# Pure_ADSR.net
KiCad netlist of a schematic drawn in EAGLE
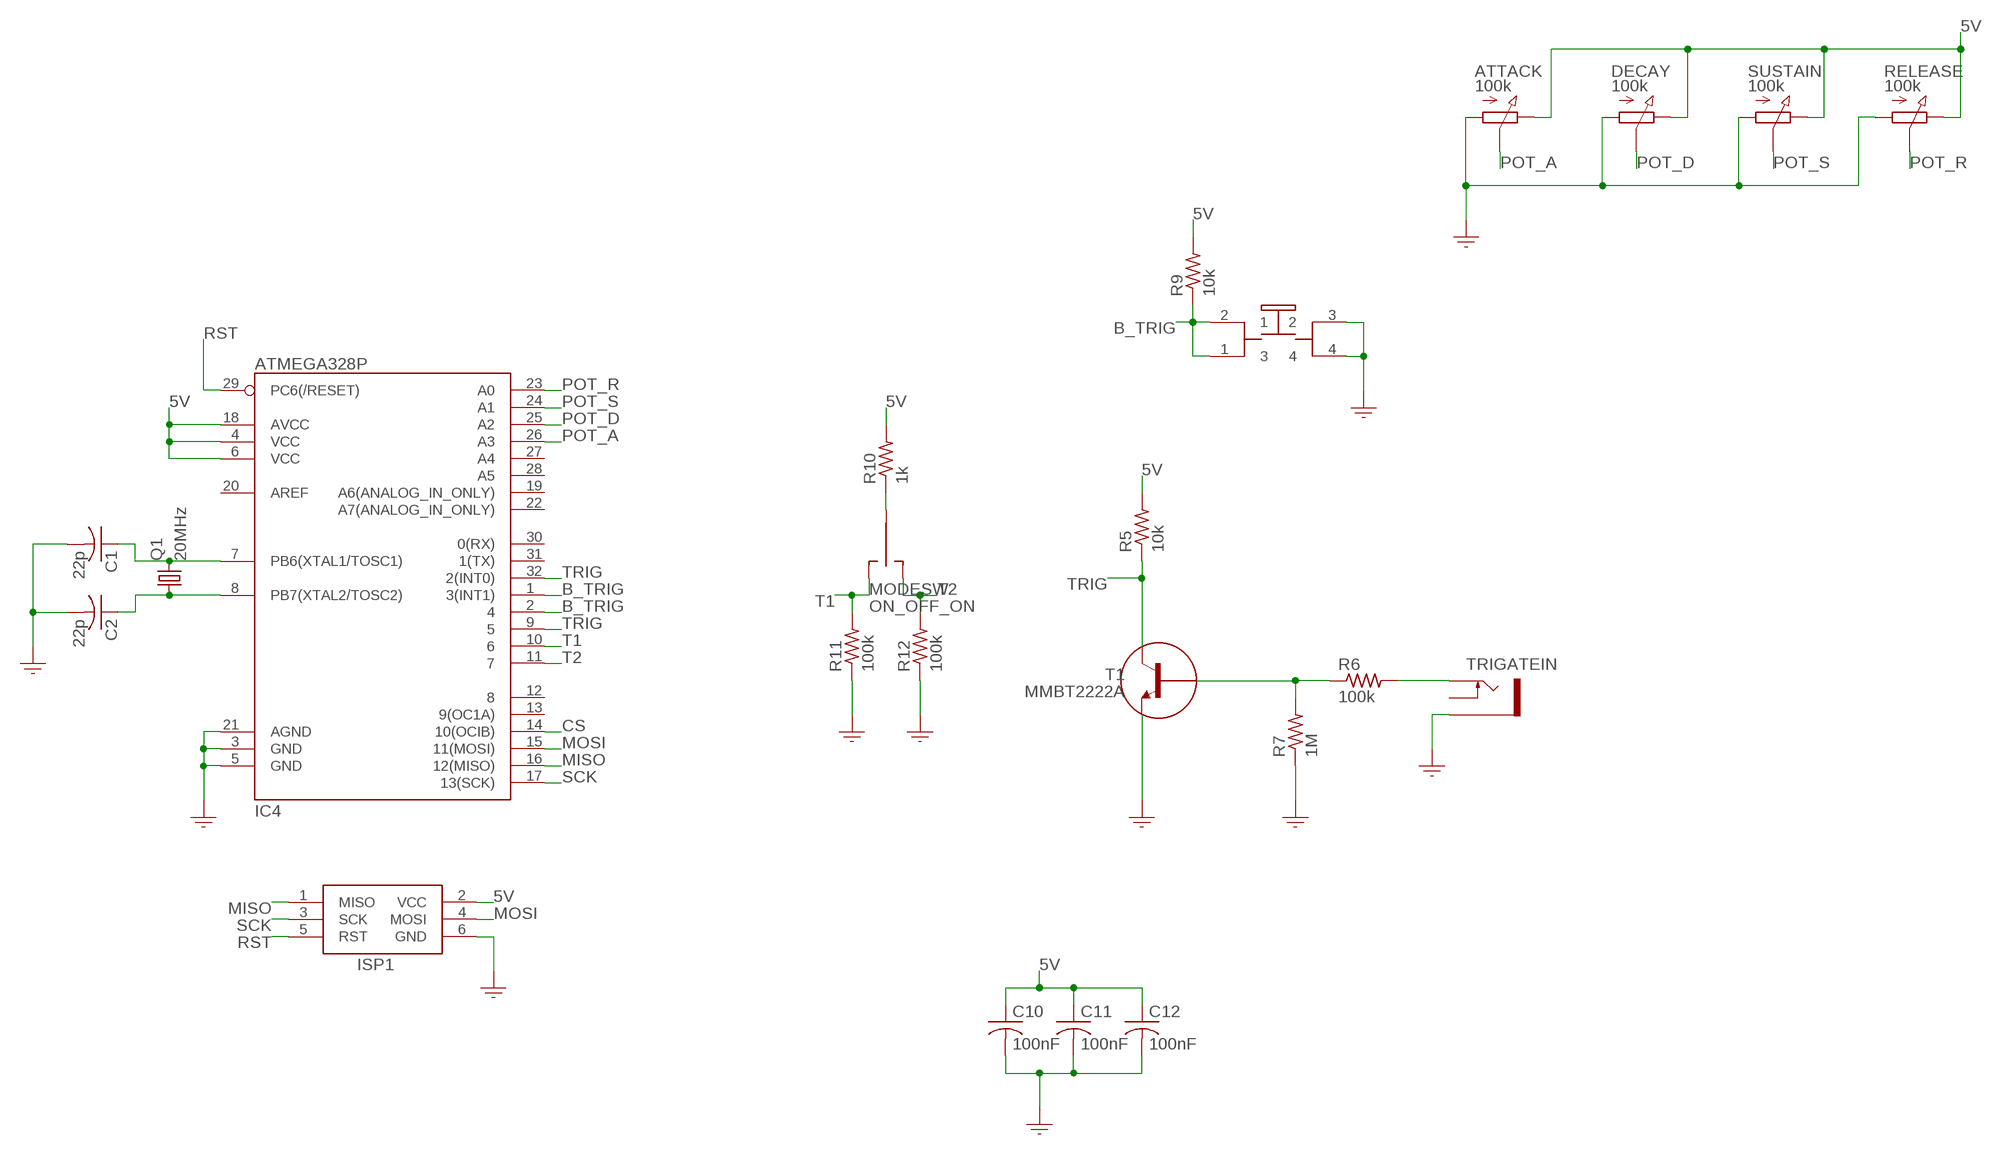
[diagram p0: schematic, sheet 1]
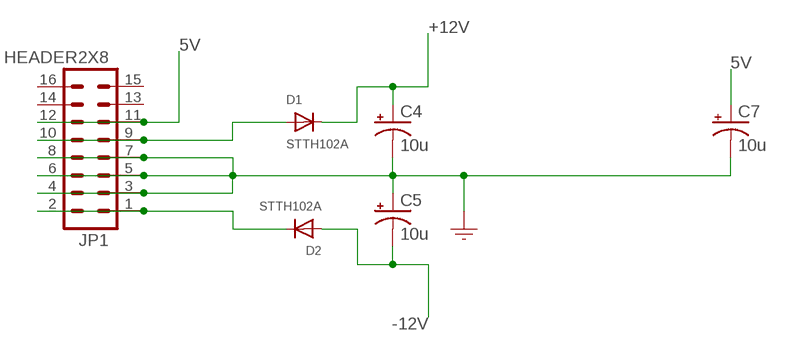
[diagram p1: schematic, sheet 2]
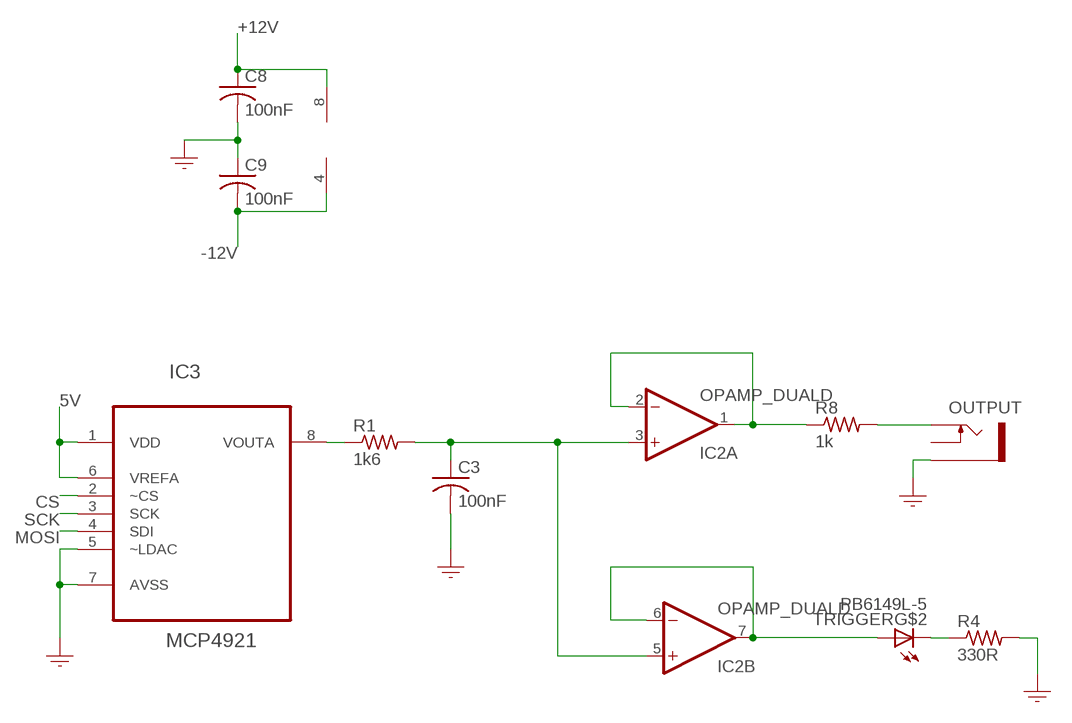
[diagram p2: schematic, sheet 3]

(export (version "E")
  (design (tool "Eeschema 10.0.6"))
  (components
    (comp (ref "C4")
      (value "10u")
      (footprint "eagle-import:153CLV-0505")
      (libsource (lib "eagle-import") (part "CAPACITOR_POL-US153CLV-0505"))
    )
    (comp (ref "C5")
      (value "10u")
      (footprint "eagle-import:153CLV-0505")
      (libsource (lib "eagle-import") (part "CAPACITOR_POL-US153CLV-0505"))
    )
    (comp (ref "C7")
      (value "10u")
      (footprint "eagle-import:153CLV-0505")
      (libsource (lib "eagle-import") (part "CAPACITOR_POL-US153CLV-0505"))
    )
    (comp (ref "D1")
      (value "STTH102A")
      (footprint "eagle-import:SMADIODE")
      (libsource (lib "eagle-import") (part "DIODESMA"))
    )
    (comp (ref "D2")
      (value "STTH102A")
      (footprint "eagle-import:SMADIODE")
      (libsource (lib "eagle-import") (part "DIODESMA"))
    )
    (comp (ref "JP1")
      (value "HEADER2X8")
      (footprint "eagle-import:POWER_SHROUDED")
      (libsource (lib "eagle-import") (part "HEADER2X8"))
    )
    (comp (ref "C3")
      (value "100nF")
      (footprint "eagle-import:C0805")
      (libsource (lib "eagle-import") (part "CAPACITOR-USC0805"))
    )
    (comp (ref "C8")
      (value "100nF")
      (footprint "eagle-import:C0805")
      (libsource (lib "eagle-import") (part "CAPACITOR-USC0805"))
    )
    (comp (ref "C9")
      (value "100nF")
      (footprint "eagle-import:C0805")
      (libsource (lib "eagle-import") (part "CAPACITOR-USC0805"))
    )
    (comp (ref "IC2")
      (value "OPAMP_DUALD")
      (footprint "eagle-import:SO08")
      (libsource (lib "eagle-import") (part "OPAMP_DUALD"))
    )
    (comp (ref "IC3")
      (value "MCP4921")
      (footprint "eagle-import:SOIC8")
      (libsource (lib "eagle-import") (part "DAC_SINGLE_12B_MCP4921"))
    )
    (comp (ref "OUTPUT")
      (value "SOCKET_MONO_3.5MMPJ301M-12")
      (footprint "eagle-import:PJ301M-12")
      (libsource (lib "eagle-import") (part "SOCKET_MONO_3.5MMPJ301M-12"))
    )
    (comp (ref "R1")
      (value "1k6")
      (footprint "eagle-import:R0805")
      (libsource (lib "eagle-import") (part "RESISTOR_USR0805"))
    )
    (comp (ref "R4")
      (value "330R")
      (footprint "eagle-import:R0805")
      (libsource (lib "eagle-import") (part "RESISTOR_USR0805"))
    )
    (comp (ref "R8")
      (value "1k")
      (footprint "eagle-import:R0805")
      (libsource (lib "eagle-import") (part "RESISTOR_USR0805"))
    )
    (comp (ref "TRIGGER")
      (value "PB6149L-5")
      (footprint "eagle-import:PB6149L")
      (libsource (lib "eagle-import") (part "SWITCH_PUSHBUTTON_LED"))
    )
    (comp (ref "ATTACK")
      (value "100k")
      (footprint "eagle-import:POTENTIOMETER_9MM")
      (libsource (lib "eagle-import") (part "RESISTOR_VARIABLE9MM_POT"))
    )
    (comp (ref "C1")
      (value "22p")
      (footprint "eagle-import:C0805")
      (libsource (lib "eagle-import") (part "CAPACITOR-USC0805"))
    )
    (comp (ref "C2")
      (value "22p")
      (footprint "eagle-import:C0805")
      (libsource (lib "eagle-import") (part "CAPACITOR-USC0805"))
    )
    (comp (ref "C10")
      (value "100nF")
      (footprint "eagle-import:C0805")
      (libsource (lib "eagle-import") (part "CAPACITOR-USC0805"))
    )
    (comp (ref "C11")
      (value "100nF")
      (footprint "eagle-import:C0805")
      (libsource (lib "eagle-import") (part "CAPACITOR-USC0805"))
    )
    (comp (ref "C12")
      (value "100nF")
      (footprint "eagle-import:C0805")
      (libsource (lib "eagle-import") (part "CAPACITOR-USC0805"))
    )
    (comp (ref "DECAY")
      (value "100k")
      (footprint "eagle-import:POTENTIOMETER_9MM")
      (libsource (lib "eagle-import") (part "RESISTOR_VARIABLE9MM_POT"))
    )
    (comp (ref "IC4")
      (value "ATMEGA328P")
      (footprint "eagle-import:TQFP32-08")
      (libsource (lib "eagle-import") (part "MICROPROCESSOR_ATMEGA328_SMT"))
    )
    (comp (ref "ISP1")
      (value "HEADER2X3-6")
      (footprint "eagle-import:AVRISP")
      (libsource (lib "eagle-import") (part "HEADER2X3-6"))
    )
    (comp (ref "MODESW")
      (value "ON_OFF_ON")
      (footprint "eagle-import:TOGGLE_SW")
      (libsource (lib "eagle-import") (part "SWITCH_TOGGLE_SPDT"))
    )
    (comp (ref "Q1")
      (value "20MHz")
      (footprint "eagle-import:HC49UP")
      (libsource (lib "eagle-import") (part "CRYSTALHC49UP"))
    )
    (comp (ref "R5")
      (value "10k")
      (footprint "eagle-import:R0805")
      (libsource (lib "eagle-import") (part "RESISTOR_USR0805"))
    )
    (comp (ref "R6")
      (value "100k")
      (footprint "eagle-import:R0805")
      (libsource (lib "eagle-import") (part "RESISTOR_USR0805"))
    )
    (comp (ref "R7")
      (value "1M")
      (footprint "eagle-import:R0805")
      (libsource (lib "eagle-import") (part "RESISTOR_USR0805"))
    )
    (comp (ref "R9")
      (value "10k")
      (footprint "eagle-import:R0805")
      (libsource (lib "eagle-import") (part "RESISTOR_USR0805"))
    )
    (comp (ref "R10")
      (value "1k")
      (footprint "eagle-import:R0805")
      (libsource (lib "eagle-import") (part "RESISTOR_USR0805"))
    )
    (comp (ref "R11")
      (value "100k")
      (footprint "eagle-import:R0805")
      (libsource (lib "eagle-import") (part "RESISTOR_USR0805"))
    )
    (comp (ref "R12")
      (value "100k")
      (footprint "eagle-import:R0805")
      (libsource (lib "eagle-import") (part "RESISTOR_USR0805"))
    )
    (comp (ref "RELEASE")
      (value "100k")
      (footprint "eagle-import:POTENTIOMETER_9MM")
      (libsource (lib "eagle-import") (part "RESISTOR_VARIABLE9MM_POT"))
    )
    (comp (ref "SUSTAIN")
      (value "100k")
      (footprint "eagle-import:POTENTIOMETER_9MM")
      (libsource (lib "eagle-import") (part "RESISTOR_VARIABLE9MM_POT"))
    )
    (comp (ref "T1")
      (value "MMBT2222A")
      (footprint "eagle-import:SOT23")
      (libsource (lib "eagle-import") (part "TRANSISTOR_NPNMMBT2222A"))
    )
    (comp (ref "TRIGATEIN")
      (value "SOCKET_MONO_3.5MMPJ301M-12")
      (footprint "eagle-import:PJ301M-12")
      (libsource (lib "eagle-import") (part "SOCKET_MONO_3.5MMPJ301M-12"))
    )
  )
  (nets
    (net (code "1") (name "+12V") (class "Default")
      (node (ref "C4") (pin "+") (pinfunction "+_+") (pintype "passive"))
      (node (ref "C8") (pin "1") (pinfunction "1_1") (pintype "passive"))
      (node (ref "D1") (pin "C") (pinfunction "C_C") (pintype "passive"))
      (node (ref "IC2") (pin "8") (pinfunction "V+_8") (pintype "power_in"))
    )
    (net (code "2") (name "-12V") (class "Default")
      (node (ref "C5") (pin "-") (pinfunction "-_-") (pintype "passive"))
      (node (ref "C9") (pin "2") (pinfunction "2_2") (pintype "passive"))
      (node (ref "D2") (pin "A") (pinfunction "A_A") (pintype "passive"))
      (node (ref "IC2") (pin "4") (pinfunction "V-_4") (pintype "power_in"))
    )
    (net (code "3") (name "5V") (class "Default")
      (node (ref "ATTACK") (pin "P$3") (pinfunction "3_P$3") (pintype "passive"))
      (node (ref "C10") (pin "1") (pinfunction "1_1") (pintype "passive"))
      (node (ref "C11") (pin "1") (pinfunction "1_1") (pintype "passive"))
      (node (ref "C12") (pin "1") (pinfunction "1_1") (pintype "passive"))
      (node (ref "C7") (pin "+") (pinfunction "+_+") (pintype "passive"))
      (node (ref "DECAY") (pin "P$3") (pinfunction "3_P$3") (pintype "passive"))
      (node (ref "IC3") (pin "1") (pinfunction "VDD_1") (pintype "power_in"))
      (node (ref "IC3") (pin "6") (pinfunction "VREFA_6") (pintype "input"))
      (node (ref "IC4") (pin "18") (pinfunction "AVCC_18") (pintype "bidirectional"))
      (node (ref "IC4") (pin "4") (pinfunction "VCC_4") (pintype "bidirectional"))
      (node (ref "IC4") (pin "6") (pinfunction "VCC_6") (pintype "bidirectional"))
      (node (ref "ISP1") (pin "2") (pinfunction "VCC_2") (pintype "power_in"))
      (node (ref "JP1") (pin "11") (pinfunction "11_11") (pintype "passive"))
      (node (ref "JP1") (pin "12") (pinfunction "12_12") (pintype "passive"))
      (node (ref "R10") (pin "2") (pinfunction "2_2") (pintype "passive"))
      (node (ref "R5") (pin "2") (pinfunction "2_2") (pintype "passive"))
      (node (ref "R9") (pin "2") (pinfunction "2_2") (pintype "passive"))
      (node (ref "RELEASE") (pin "P$3") (pinfunction "3_P$3") (pintype "passive"))
      (node (ref "SUSTAIN") (pin "P$3") (pinfunction "3_P$3") (pintype "passive"))
    )
    (net (code "4") (name "B_TRIG") (class "Default")
      (node (ref "IC4") (pin "1") (pinfunction "3(INT1)_1") (pintype "bidirectional"))
      (node (ref "IC4") (pin "2") (pinfunction "4_2") (pintype "bidirectional"))
      (node (ref "R9") (pin "1") (pinfunction "1_1") (pintype "passive"))
      (node (ref "TRIGGER") (pin "1") (pinfunction "3_1") (pintype "bidirectional"))
      (node (ref "TRIGGER") (pin "2") (pinfunction "1_2") (pintype "bidirectional"))
    )
    (net (code "5") (name "CS") (class "Default")
      (node (ref "IC3") (pin "2") (pinfunction "~{CS}_2") (pintype "input"))
      (node (ref "IC4") (pin "14") (pinfunction "10(OCIB)_14") (pintype "bidirectional"))
    )
    (net (code "6") (name "GND") (class "Default")
      (node (ref "ATTACK") (pin "P$1") (pinfunction "1_P$1") (pintype "passive"))
      (node (ref "C1") (pin "2") (pinfunction "2_2") (pintype "passive"))
      (node (ref "C10") (pin "2") (pinfunction "2_2") (pintype "passive"))
      (node (ref "C11") (pin "2") (pinfunction "2_2") (pintype "passive"))
      (node (ref "C12") (pin "2") (pinfunction "2_2") (pintype "passive"))
      (node (ref "C2") (pin "2") (pinfunction "2_2") (pintype "passive"))
      (node (ref "C3") (pin "2") (pinfunction "2_2") (pintype "passive"))
      (node (ref "C4") (pin "-") (pinfunction "-_-") (pintype "passive"))
      (node (ref "C5") (pin "+") (pinfunction "+_+") (pintype "passive"))
      (node (ref "C7") (pin "-") (pinfunction "-_-") (pintype "passive"))
      (node (ref "C8") (pin "2") (pinfunction "2_2") (pintype "passive"))
      (node (ref "C9") (pin "1") (pinfunction "1_1") (pintype "passive"))
      (node (ref "DECAY") (pin "P$1") (pinfunction "1_P$1") (pintype "passive"))
      (node (ref "IC3") (pin "5") (pinfunction "~{LDAC}_5") (pintype "input"))
      (node (ref "IC3") (pin "7") (pinfunction "AVSS_7") (pintype "passive"))
      (node (ref "IC4") (pin "21") (pinfunction "AGND_21") (pintype "bidirectional"))
      (node (ref "IC4") (pin "3") (pinfunction "GND_3") (pintype "bidirectional"))
      (node (ref "IC4") (pin "5") (pinfunction "GND_5") (pintype "bidirectional"))
      (node (ref "ISP1") (pin "6") (pinfunction "GND_6") (pintype "power_in"))
      (node (ref "JP1") (pin "3") (pinfunction "3_3") (pintype "passive"))
      (node (ref "JP1") (pin "4") (pinfunction "4_4") (pintype "passive"))
      (node (ref "JP1") (pin "5") (pinfunction "5_5") (pintype "passive"))
      (node (ref "JP1") (pin "6") (pinfunction "6_6") (pintype "passive"))
      (node (ref "JP1") (pin "7") (pinfunction "7_7") (pintype "passive"))
      (node (ref "JP1") (pin "8") (pinfunction "8_8") (pintype "passive"))
      (node (ref "OUTPUT") (pin "GND") (pinfunction "SLEEVE_GND") (pintype "passive"))
      (node (ref "R11") (pin "1") (pinfunction "1_1") (pintype "passive"))
      (node (ref "R12") (pin "1") (pinfunction "1_1") (pintype "passive"))
      (node (ref "R4") (pin "2") (pinfunction "2_2") (pintype "passive"))
      (node (ref "R7") (pin "1") (pinfunction "1_1") (pintype "passive"))
      (node (ref "RELEASE") (pin "P$1") (pinfunction "1_P$1") (pintype "passive"))
      (node (ref "SUSTAIN") (pin "P$1") (pinfunction "1_P$1") (pintype "passive"))
      (node (ref "T1") (pin "2") (pinfunction "E_2") (pintype "passive"))
      (node (ref "TRIGATEIN") (pin "GND") (pinfunction "SLEEVE_GND") (pintype "passive"))
      (node (ref "TRIGGER") (pin "3") (pinfunction "2_3") (pintype "bidirectional"))
      (node (ref "TRIGGER") (pin "4") (pinfunction "4_4") (pintype "bidirectional"))
    )
    (net (code "7") (name "MISO") (class "Default")
      (node (ref "IC4") (pin "16") (pinfunction "12(MISO)_16") (pintype "bidirectional"))
      (node (ref "ISP1") (pin "1") (pinfunction "MISO_1") (pintype "input"))
    )
    (net (code "8") (name "MOSI") (class "Default")
      (node (ref "IC3") (pin "4") (pinfunction "SDI_4") (pintype "input"))
      (node (ref "IC4") (pin "15") (pinfunction "11(MOSI)_15") (pintype "bidirectional"))
      (node (ref "ISP1") (pin "4") (pinfunction "MOSI_4") (pintype "output"))
    )
    (net (code "9") (name "Net-(D1-PadA)") (class "Default")
      (node (ref "D1") (pin "A") (pinfunction "A_A") (pintype "passive"))
      (node (ref "JP1") (pin "10") (pinfunction "10_10") (pintype "passive"))
      (node (ref "JP1") (pin "9") (pinfunction "9_9") (pintype "passive"))
    )
    (net (code "10") (name "Net-(D2-PadC)") (class "Default")
      (node (ref "D2") (pin "C") (pinfunction "C_C") (pintype "passive"))
      (node (ref "JP1") (pin "1") (pinfunction "1_1") (pintype "passive"))
      (node (ref "JP1") (pin "2") (pinfunction "2_2") (pintype "passive"))
    )
    (net (code "11") (name "Net-(IC2A-+IN)") (class "Default")
      (node (ref "C3") (pin "1") (pinfunction "1_1") (pintype "passive"))
      (node (ref "IC2") (pin "3") (pinfunction "+IN_3") (pintype "input"))
      (node (ref "IC2") (pin "5") (pinfunction "+IN_5") (pintype "input"))
      (node (ref "R1") (pin "2") (pinfunction "2_2") (pintype "passive"))
    )
    (net (code "12") (name "Net-(IC2A--IN)") (class "Default")
      (node (ref "IC2") (pin "1") (pinfunction "OUT_1") (pintype "output"))
      (node (ref "IC2") (pin "2") (pinfunction "-IN_2") (pintype "input"))
      (node (ref "R8") (pin "1") (pinfunction "1_1") (pintype "passive"))
    )
    (net (code "13") (name "Net-(IC2B--IN)") (class "Default")
      (node (ref "IC2") (pin "6") (pinfunction "-IN_6") (pintype "input"))
      (node (ref "IC2") (pin "7") (pinfunction "OUT_7") (pintype "output"))
      (node (ref "TRIGGER") (pin "A") (pinfunction "A_A") (pintype "passive"))
    )
    (net (code "14") (name "Net-(IC3-VOUTA)") (class "Default")
      (node (ref "IC3") (pin "8") (pinfunction "VOUTA_8") (pintype "output"))
      (node (ref "R1") (pin "1") (pinfunction "1_1") (pintype "passive"))
    )
    (net (code "15") (name "Net-(IC4-PB6(XTAL1{slash}TOSC1))") (class "Default")
      (node (ref "C1") (pin "1") (pinfunction "1_1") (pintype "passive"))
      (node (ref "IC4") (pin "7") (pinfunction "PB6(XTAL1/TOSC1)_7") (pintype "bidirectional"))
      (node (ref "Q1") (pin "2") (pinfunction "2_2") (pintype "passive"))
    )
    (net (code "16") (name "Net-(IC4-PB7(XTAL2{slash}TOSC2))") (class "Default")
      (node (ref "C2") (pin "1") (pinfunction "1_1") (pintype "passive"))
      (node (ref "IC4") (pin "8") (pinfunction "PB7(XTAL2/TOSC2)_8") (pintype "bidirectional"))
      (node (ref "Q1") (pin "1") (pinfunction "1_1") (pintype "passive"))
    )
    (net (code "17") (name "Net-(MODESW-P)") (class "Default")
      (node (ref "MODESW") (pin "2") (pinfunction "P_2") (pintype "passive"))
      (node (ref "R10") (pin "1") (pinfunction "1_1") (pintype "passive"))
    )
    (net (code "18") (name "Net-(OUTPUT-PadTIP)") (class "Default")
      (node (ref "OUTPUT") (pin "TIP") (pinfunction "TIP_TIP") (pintype "passive"))
      (node (ref "R8") (pin "2") (pinfunction "2_2") (pintype "passive"))
    )
    (net (code "19") (name "Net-(R6-Pad2)") (class "Default")
      (node (ref "R6") (pin "2") (pinfunction "2_2") (pintype "passive"))
      (node (ref "TRIGATEIN") (pin "TIP") (pinfunction "TIP_TIP") (pintype "passive"))
    )
    (net (code "20") (name "Net-(T1-B)") (class "Default")
      (node (ref "R6") (pin "1") (pinfunction "1_1") (pintype "passive"))
      (node (ref "R7") (pin "2") (pinfunction "2_2") (pintype "passive"))
      (node (ref "T1") (pin "1") (pinfunction "B_1") (pintype "passive"))
    )
    (net (code "21") (name "Net-(TRIGGERB-C)") (class "Default")
      (node (ref "R4") (pin "1") (pinfunction "1_1") (pintype "passive"))
      (node (ref "TRIGGER") (pin "K") (pinfunction "C_K") (pintype "passive"))
    )
    (net (code "22") (name "POT_A") (class "Default")
      (node (ref "ATTACK") (pin "P$2") (pinfunction "2_P$2") (pintype "passive"))
      (node (ref "IC4") (pin "26") (pinfunction "A3_26") (pintype "bidirectional"))
    )
    (net (code "23") (name "POT_D") (class "Default")
      (node (ref "DECAY") (pin "P$2") (pinfunction "2_P$2") (pintype "passive"))
      (node (ref "IC4") (pin "25") (pinfunction "A2_25") (pintype "bidirectional"))
    )
    (net (code "24") (name "POT_R") (class "Default")
      (node (ref "IC4") (pin "23") (pinfunction "A0_23") (pintype "bidirectional"))
      (node (ref "RELEASE") (pin "P$2") (pinfunction "2_P$2") (pintype "passive"))
    )
    (net (code "25") (name "POT_S") (class "Default")
      (node (ref "IC4") (pin "24") (pinfunction "A1_24") (pintype "bidirectional"))
      (node (ref "SUSTAIN") (pin "P$2") (pinfunction "2_P$2") (pintype "passive"))
    )
    (net (code "26") (name "RST") (class "Default")
      (node (ref "IC4") (pin "29") (pinfunction "PC6(/RESET)_29") (pintype "bidirectional"))
      (node (ref "ISP1") (pin "5") (pinfunction "RST_5") (pintype "output"))
    )
    (net (code "27") (name "SCK") (class "Default")
      (node (ref "IC3") (pin "3") (pinfunction "SCK_3") (pintype "input"))
      (node (ref "IC4") (pin "17") (pinfunction "13(SCK)_17") (pintype "bidirectional"))
      (node (ref "ISP1") (pin "3") (pinfunction "SCK_3") (pintype "output"))
    )
    (net (code "28") (name "T1") (class "Default")
      (node (ref "IC4") (pin "10") (pinfunction "6_10") (pintype "bidirectional"))
      (node (ref "MODESW") (pin "3") (pinfunction "S_3") (pintype "passive"))
      (node (ref "R11") (pin "2") (pinfunction "2_2") (pintype "passive"))
    )
    (net (code "29") (name "T2") (class "Default")
      (node (ref "IC4") (pin "11") (pinfunction "7_11") (pintype "bidirectional"))
      (node (ref "MODESW") (pin "1") (pinfunction "O_1") (pintype "passive"))
      (node (ref "R12") (pin "2") (pinfunction "2_2") (pintype "passive"))
    )
    (net (code "30") (name "TRIG") (class "Default")
      (node (ref "IC4") (pin "32") (pinfunction "2(INT0)_32") (pintype "bidirectional"))
      (node (ref "IC4") (pin "9") (pinfunction "5_9") (pintype "bidirectional"))
      (node (ref "R5") (pin "1") (pinfunction "1_1") (pintype "passive"))
      (node (ref "T1") (pin "3") (pinfunction "C_3") (pintype "passive"))
    )
    (net (code "31") (name "unconnected-(IC4-0(RX)-Pad30)") (class "Default")
      (node (ref "IC4") (pin "30") (pinfunction "0(RX)_30") (pintype "bidirectional"))
    )
    (net (code "32") (name "unconnected-(IC4-1(TX)-Pad31)") (class "Default")
      (node (ref "IC4") (pin "31") (pinfunction "1(TX)_31") (pintype "bidirectional"))
    )
    (net (code "33") (name "unconnected-(IC4-8-Pad12)") (class "Default")
      (node (ref "IC4") (pin "12") (pinfunction "8_12") (pintype "bidirectional"))
    )
    (net (code "34") (name "unconnected-(IC4-9(OC1A)-Pad13)") (class "Default")
      (node (ref "IC4") (pin "13") (pinfunction "9(OC1A)_13") (pintype "bidirectional"))
    )
    (net (code "35") (name "unconnected-(IC4-A4-Pad27)") (class "Default")
      (node (ref "IC4") (pin "27") (pinfunction "A4_27") (pintype "bidirectional"))
    )
    (net (code "36") (name "unconnected-(IC4-A5-Pad28)") (class "Default")
      (node (ref "IC4") (pin "28") (pinfunction "A5_28") (pintype "bidirectional"))
    )
    (net (code "37") (name "unconnected-(IC4-A6(ANALOG_IN_ONLY)-Pad19)") (class "Default")
      (node (ref "IC4") (pin "19") (pinfunction "A6(ANALOG_IN_ONLY)_19") (pintype "bidirectional"))
    )
    (net (code "38") (name "unconnected-(IC4-A7(ANALOG_IN_ONLY)-Pad22)") (class "Default")
      (node (ref "IC4") (pin "22") (pinfunction "A7(ANALOG_IN_ONLY)_22") (pintype "bidirectional"))
    )
    (net (code "39") (name "unconnected-(IC4-AREF-Pad20)") (class "Default")
      (node (ref "IC4") (pin "20") (pinfunction "AREF_20") (pintype "bidirectional"))
    )
    (net (code "40") (name "unconnected-(JP1-Pad13)") (class "Default")
      (node (ref "JP1") (pin "13") (pinfunction "13_13") (pintype "passive"))
    )
    (net (code "41") (name "unconnected-(JP1-Pad14)") (class "Default")
      (node (ref "JP1") (pin "14") (pinfunction "14_14") (pintype "passive"))
    )
    (net (code "42") (name "unconnected-(JP1-Pad15)") (class "Default")
      (node (ref "JP1") (pin "15") (pinfunction "15_15") (pintype "passive"))
    )
    (net (code "43") (name "unconnected-(JP1-Pad16)") (class "Default")
      (node (ref "JP1") (pin "16") (pinfunction "16_16") (pintype "passive"))
    )
    (net (code "44") (name "unconnected-(OUTPUT-SWITCH-PadNORM)") (class "Default")
      (node (ref "OUTPUT") (pin "NORM") (pinfunction "SWITCH_NORM") (pintype "passive"))
    )
    (net (code "45") (name "unconnected-(TRIGATEIN-SWITCH-PadNORM)") (class "Default")
      (node (ref "TRIGATEIN") (pin "NORM") (pinfunction "SWITCH_NORM") (pintype "passive"))
    )
  )
)
